# lights.net
KiCad netlist of a schematic drawn in EAGLE
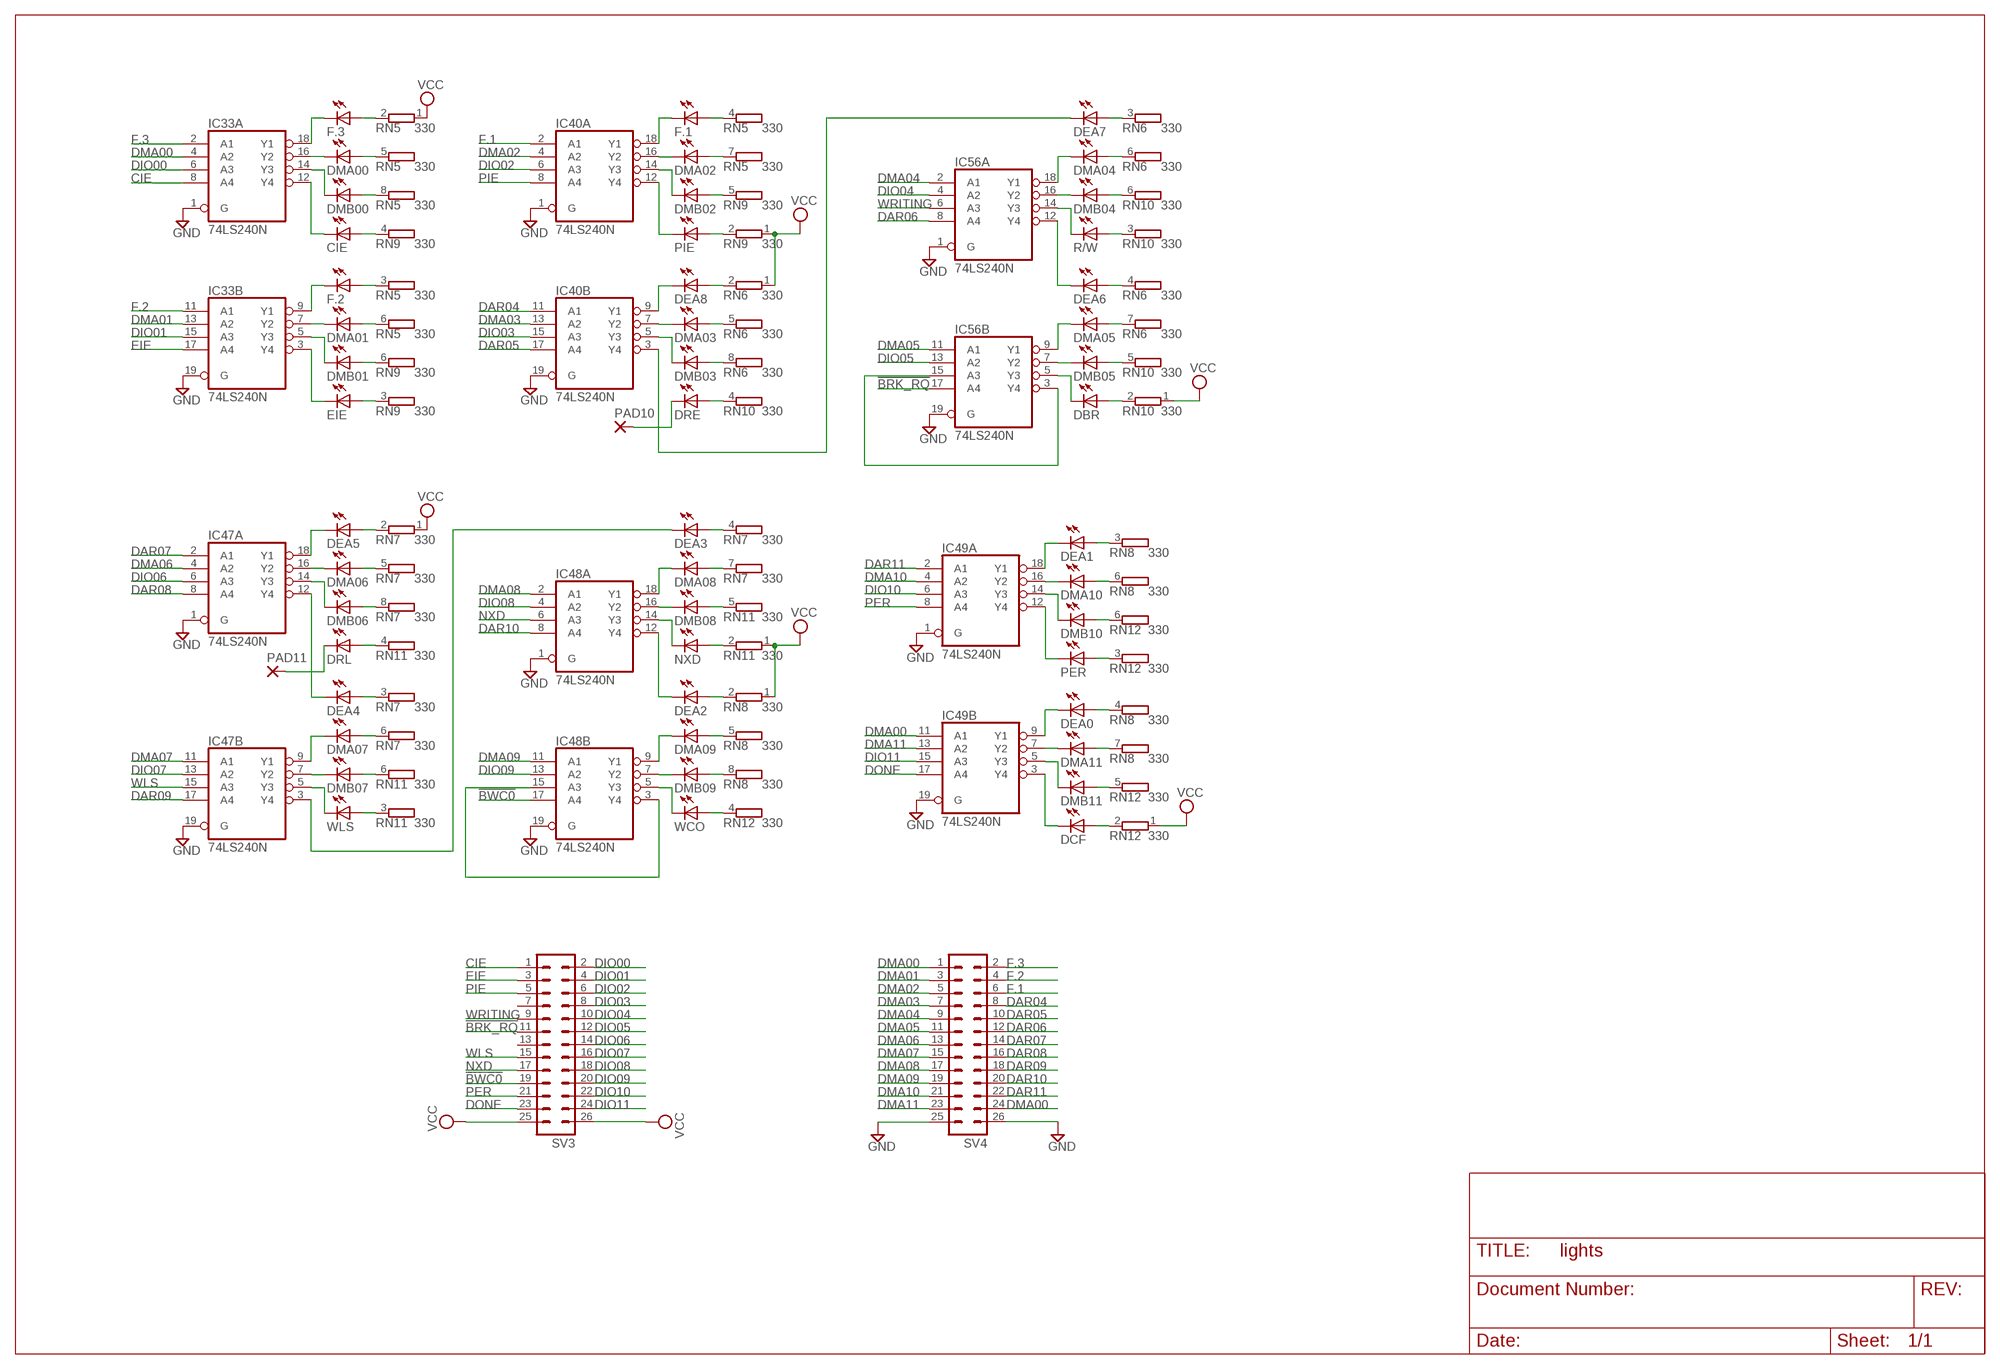
[diagram p0: schematic, sheet 1]

(export (version "E")
  (design (tool "Eeschema 10.0.6"))
  (components
    (comp (ref "CIE")
      (value "LED5MM")
      (footprint "eagle-import:LED5MM")
      (libsource (lib "eagle-import") (part "LED5MM"))
    )
    (comp (ref "DBR")
      (value "LED5MM")
      (footprint "eagle-import:LED5MM")
      (libsource (lib "eagle-import") (part "LED5MM"))
    )
    (comp (ref "DCF")
      (value "LED5MM")
      (footprint "eagle-import:LED5MM")
      (libsource (lib "eagle-import") (part "LED5MM"))
    )
    (comp (ref "DEA0")
      (value "LED5MM")
      (footprint "eagle-import:LED5MM")
      (libsource (lib "eagle-import") (part "LED5MM"))
    )
    (comp (ref "DEA1")
      (value "LED5MM")
      (footprint "eagle-import:LED5MM")
      (libsource (lib "eagle-import") (part "LED5MM"))
    )
    (comp (ref "DEA2")
      (value "LED5MM")
      (footprint "eagle-import:LED5MM")
      (libsource (lib "eagle-import") (part "LED5MM"))
    )
    (comp (ref "DEA3")
      (value "LED5MM")
      (footprint "eagle-import:LED5MM")
      (libsource (lib "eagle-import") (part "LED5MM"))
    )
    (comp (ref "DEA4")
      (value "LED5MM")
      (footprint "eagle-import:LED5MM")
      (libsource (lib "eagle-import") (part "LED5MM"))
    )
    (comp (ref "DEA5")
      (value "LED5MM")
      (footprint "eagle-import:LED5MM")
      (libsource (lib "eagle-import") (part "LED5MM"))
    )
    (comp (ref "DEA6")
      (value "LED5MM")
      (footprint "eagle-import:LED5MM")
      (libsource (lib "eagle-import") (part "LED5MM"))
    )
    (comp (ref "DEA7")
      (value "LED5MM")
      (footprint "eagle-import:LED5MM")
      (libsource (lib "eagle-import") (part "LED5MM"))
    )
    (comp (ref "DEA8")
      (value "LED5MM")
      (footprint "eagle-import:LED5MM")
      (libsource (lib "eagle-import") (part "LED5MM"))
    )
    (comp (ref "DMA00")
      (value "LED5MM")
      (footprint "eagle-import:LED5MM")
      (libsource (lib "eagle-import") (part "LED5MM"))
    )
    (comp (ref "DMA01")
      (value "LED5MM")
      (footprint "eagle-import:LED5MM")
      (libsource (lib "eagle-import") (part "LED5MM"))
    )
    (comp (ref "DMA02")
      (value "LED5MM")
      (footprint "eagle-import:LED5MM")
      (libsource (lib "eagle-import") (part "LED5MM"))
    )
    (comp (ref "DMA03")
      (value "LED5MM")
      (footprint "eagle-import:LED5MM")
      (libsource (lib "eagle-import") (part "LED5MM"))
    )
    (comp (ref "DMA04")
      (value "LED5MM")
      (footprint "eagle-import:LED5MM")
      (libsource (lib "eagle-import") (part "LED5MM"))
    )
    (comp (ref "DMA05")
      (value "LED5MM")
      (footprint "eagle-import:LED5MM")
      (libsource (lib "eagle-import") (part "LED5MM"))
    )
    (comp (ref "DMA06")
      (value "LED5MM")
      (footprint "eagle-import:LED5MM")
      (libsource (lib "eagle-import") (part "LED5MM"))
    )
    (comp (ref "DMA07")
      (value "LED5MM")
      (footprint "eagle-import:LED5MM")
      (libsource (lib "eagle-import") (part "LED5MM"))
    )
    (comp (ref "DMA08")
      (value "LED5MM")
      (footprint "eagle-import:LED5MM")
      (libsource (lib "eagle-import") (part "LED5MM"))
    )
    (comp (ref "DMA09")
      (value "LED5MM")
      (footprint "eagle-import:LED5MM")
      (libsource (lib "eagle-import") (part "LED5MM"))
    )
    (comp (ref "DMA10")
      (value "LED5MM")
      (footprint "eagle-import:LED5MM")
      (libsource (lib "eagle-import") (part "LED5MM"))
    )
    (comp (ref "DMA11")
      (value "LED5MM")
      (footprint "eagle-import:LED5MM")
      (libsource (lib "eagle-import") (part "LED5MM"))
    )
    (comp (ref "DMB00")
      (value "LED5MM")
      (footprint "eagle-import:LED5MM")
      (libsource (lib "eagle-import") (part "LED5MM"))
    )
    (comp (ref "DMB01")
      (value "LED5MM")
      (footprint "eagle-import:LED5MM")
      (libsource (lib "eagle-import") (part "LED5MM"))
    )
    (comp (ref "DMB02")
      (value "LED5MM")
      (footprint "eagle-import:LED5MM")
      (libsource (lib "eagle-import") (part "LED5MM"))
    )
    (comp (ref "DMB03")
      (value "LED5MM")
      (footprint "eagle-import:LED5MM")
      (libsource (lib "eagle-import") (part "LED5MM"))
    )
    (comp (ref "DMB04")
      (value "LED5MM")
      (footprint "eagle-import:LED5MM")
      (libsource (lib "eagle-import") (part "LED5MM"))
    )
    (comp (ref "DMB05")
      (value "LED5MM")
      (footprint "eagle-import:LED5MM")
      (libsource (lib "eagle-import") (part "LED5MM"))
    )
    (comp (ref "DMB06")
      (value "LED5MM")
      (footprint "eagle-import:LED5MM")
      (libsource (lib "eagle-import") (part "LED5MM"))
    )
    (comp (ref "DMB07")
      (value "LED5MM")
      (footprint "eagle-import:LED5MM")
      (libsource (lib "eagle-import") (part "LED5MM"))
    )
    (comp (ref "DMB08")
      (value "LED5MM")
      (footprint "eagle-import:LED5MM")
      (libsource (lib "eagle-import") (part "LED5MM"))
    )
    (comp (ref "DMB09")
      (value "LED5MM")
      (footprint "eagle-import:LED5MM")
      (libsource (lib "eagle-import") (part "LED5MM"))
    )
    (comp (ref "DMB10")
      (value "LED5MM")
      (footprint "eagle-import:LED5MM")
      (libsource (lib "eagle-import") (part "LED5MM"))
    )
    (comp (ref "DMB11")
      (value "LED5MM")
      (footprint "eagle-import:LED5MM")
      (libsource (lib "eagle-import") (part "LED5MM"))
    )
    (comp (ref "DRE")
      (value "LED5MM")
      (footprint "eagle-import:LED5MM")
      (libsource (lib "eagle-import") (part "LED5MM"))
    )
    (comp (ref "DRL")
      (value "LED5MM")
      (footprint "eagle-import:LED5MM")
      (libsource (lib "eagle-import") (part "LED5MM"))
    )
    (comp (ref "EIE")
      (value "LED5MM")
      (footprint "eagle-import:LED5MM")
      (libsource (lib "eagle-import") (part "LED5MM"))
    )
    (comp (ref "F.1")
      (value "LED5MM")
      (footprint "eagle-import:LED5MM")
      (libsource (lib "eagle-import") (part "LED5MM"))
    )
    (comp (ref "F.2")
      (value "LED5MM")
      (footprint "eagle-import:LED5MM")
      (libsource (lib "eagle-import") (part "LED5MM"))
    )
    (comp (ref "F.3")
      (value "LED5MM")
      (footprint "eagle-import:LED5MM")
      (libsource (lib "eagle-import") (part "LED5MM"))
    )
    (comp (ref "IC33")
      (value "74LS240N")
      (footprint "eagle-import:DIL20")
      (libsource (lib "eagle-import") (part "74240NLS"))
    )
    (comp (ref "IC40")
      (value "74LS240N")
      (footprint "eagle-import:DIL20")
      (libsource (lib "eagle-import") (part "74240NLS"))
    )
    (comp (ref "IC47")
      (value "74LS240N")
      (footprint "eagle-import:DIL20")
      (libsource (lib "eagle-import") (part "74240NLS"))
    )
    (comp (ref "IC48")
      (value "74LS240N")
      (footprint "eagle-import:DIL20")
      (libsource (lib "eagle-import") (part "74240NLS"))
    )
    (comp (ref "IC49")
      (value "74LS240N")
      (footprint "eagle-import:DIL20")
      (libsource (lib "eagle-import") (part "74240NLS"))
    )
    (comp (ref "IC56")
      (value "74LS240N")
      (footprint "eagle-import:DIL20")
      (libsource (lib "eagle-import") (part "74240NLS"))
    )
    (comp (ref "NXD")
      (value "LED5MM")
      (footprint "eagle-import:LED5MM")
      (libsource (lib "eagle-import") (part "LED5MM"))
    )
    (comp (ref "PAD10")
      (value "1,6/0,8")
      (footprint "eagle-import:1,6_0,8")
      (libsource (lib "eagle-import") (part "1,6/0,8"))
    )
    (comp (ref "PAD11")
      (value "1,6/0,8")
      (footprint "eagle-import:1,6_0,8")
      (libsource (lib "eagle-import") (part "1,6/0,8"))
    )
    (comp (ref "PER")
      (value "LED5MM")
      (footprint "eagle-import:LED5MM")
      (libsource (lib "eagle-import") (part "LED5MM"))
    )
    (comp (ref "PIE")
      (value "LED5MM")
      (footprint "eagle-import:LED5MM")
      (libsource (lib "eagle-import") (part "LED5MM"))
    )
    (comp (ref "R/W")
      (value "LED5MM")
      (footprint "eagle-import:LED5MM")
      (libsource (lib "eagle-import") (part "LED5MM"))
    )
    (comp (ref "RN5")
      (value "330")
      (footprint "eagle-import:SIL8")
      (libsource (lib "eagle-import") (part "GE07RP"))
    )
    (comp (ref "RN6")
      (value "330")
      (footprint "eagle-import:SIL8")
      (libsource (lib "eagle-import") (part "GE07RP"))
    )
    (comp (ref "RN7")
      (value "330")
      (footprint "eagle-import:SIL8")
      (libsource (lib "eagle-import") (part "GE07RP"))
    )
    (comp (ref "RN8")
      (value "330")
      (footprint "eagle-import:SIL8")
      (libsource (lib "eagle-import") (part "GE07RP"))
    )
    (comp (ref "RN9")
      (value "330")
      (footprint "eagle-import:SIL6")
      (libsource (lib "eagle-import") (part "GE05RP"))
    )
    (comp (ref "RN10")
      (value "330")
      (footprint "eagle-import:SIL6")
      (libsource (lib "eagle-import") (part "GE05RP"))
    )
    (comp (ref "RN11")
      (value "330")
      (footprint "eagle-import:SIL6")
      (libsource (lib "eagle-import") (part "GE05RP"))
    )
    (comp (ref "RN12")
      (value "330")
      (footprint "eagle-import:SIL6")
      (libsource (lib "eagle-import") (part "GE05RP"))
    )
    (comp (ref "SV3")
      (value "MA13-2")
      (footprint "eagle-import:MA13-2")
      (libsource (lib "eagle-import") (part "MA13-2"))
    )
    (comp (ref "SV4")
      (value "MA13-2")
      (footprint "eagle-import:MA13-2")
      (libsource (lib "eagle-import") (part "MA13-2"))
    )
    (comp (ref "WCO")
      (value "LED5MM")
      (footprint "eagle-import:LED5MM")
      (libsource (lib "eagle-import") (part "LED5MM"))
    )
    (comp (ref "WLS")
      (value "LED5MM")
      (footprint "eagle-import:LED5MM")
      (libsource (lib "eagle-import") (part "LED5MM"))
    )
  )
  (nets
    (net (code "1") (name "/CIE") (class "Default")
      (node (ref "IC33") (pin "8") (pinfunction "A4_8") (pintype "input"))
      (node (ref "SV3") (pin "1") (pinfunction "1_1") (pintype "passive"))
    )
    (net (code "2") (name "/DAR04") (class "Default")
      (node (ref "IC40") (pin "11") (pinfunction "A1_11") (pintype "input"))
      (node (ref "SV4") (pin "8") (pinfunction "8_8") (pintype "passive"))
    )
    (net (code "3") (name "/DAR05") (class "Default")
      (node (ref "IC40") (pin "17") (pinfunction "A4_17") (pintype "input"))
      (node (ref "SV4") (pin "10") (pinfunction "10_10") (pintype "passive"))
    )
    (net (code "4") (name "/DAR06") (class "Default")
      (node (ref "IC56") (pin "8") (pinfunction "A4_8") (pintype "input"))
      (node (ref "SV4") (pin "12") (pinfunction "12_12") (pintype "passive"))
    )
    (net (code "5") (name "/DAR07") (class "Default")
      (node (ref "IC47") (pin "2") (pinfunction "A1_2") (pintype "input"))
      (node (ref "SV4") (pin "14") (pinfunction "14_14") (pintype "passive"))
    )
    (net (code "6") (name "/DAR08") (class "Default")
      (node (ref "IC47") (pin "8") (pinfunction "A4_8") (pintype "input"))
      (node (ref "SV4") (pin "16") (pinfunction "16_16") (pintype "passive"))
    )
    (net (code "7") (name "/DAR09") (class "Default")
      (node (ref "IC47") (pin "17") (pinfunction "A4_17") (pintype "input"))
      (node (ref "SV4") (pin "18") (pinfunction "18_18") (pintype "passive"))
    )
    (net (code "8") (name "/DAR10") (class "Default")
      (node (ref "IC48") (pin "8") (pinfunction "A4_8") (pintype "input"))
      (node (ref "SV4") (pin "20") (pinfunction "20_20") (pintype "passive"))
    )
    (net (code "9") (name "/DAR11") (class "Default")
      (node (ref "IC49") (pin "2") (pinfunction "A1_2") (pintype "input"))
      (node (ref "SV4") (pin "22") (pinfunction "22_22") (pintype "passive"))
    )
    (net (code "10") (name "/DIO00") (class "Default")
      (node (ref "IC33") (pin "6") (pinfunction "A3_6") (pintype "input"))
      (node (ref "SV3") (pin "2") (pinfunction "2_2") (pintype "passive"))
    )
    (net (code "11") (name "/DIO01") (class "Default")
      (node (ref "IC33") (pin "15") (pinfunction "A3_15") (pintype "input"))
      (node (ref "SV3") (pin "4") (pinfunction "4_4") (pintype "passive"))
    )
    (net (code "12") (name "/DIO02") (class "Default")
      (node (ref "IC40") (pin "6") (pinfunction "A3_6") (pintype "input"))
      (node (ref "SV3") (pin "6") (pinfunction "6_6") (pintype "passive"))
    )
    (net (code "13") (name "/DIO03") (class "Default")
      (node (ref "IC40") (pin "15") (pinfunction "A3_15") (pintype "input"))
      (node (ref "SV3") (pin "8") (pinfunction "8_8") (pintype "passive"))
    )
    (net (code "14") (name "/DIO04") (class "Default")
      (node (ref "IC56") (pin "4") (pinfunction "A2_4") (pintype "input"))
      (node (ref "SV3") (pin "10") (pinfunction "10_10") (pintype "passive"))
    )
    (net (code "15") (name "/DIO05") (class "Default")
      (node (ref "IC56") (pin "13") (pinfunction "A2_13") (pintype "input"))
      (node (ref "SV3") (pin "12") (pinfunction "12_12") (pintype "passive"))
    )
    (net (code "16") (name "/DIO06") (class "Default")
      (node (ref "IC47") (pin "6") (pinfunction "A3_6") (pintype "input"))
      (node (ref "SV3") (pin "14") (pinfunction "14_14") (pintype "passive"))
    )
    (net (code "17") (name "/DIO07") (class "Default")
      (node (ref "IC47") (pin "13") (pinfunction "A2_13") (pintype "input"))
      (node (ref "SV3") (pin "16") (pinfunction "16_16") (pintype "passive"))
    )
    (net (code "18") (name "/DIO08") (class "Default")
      (node (ref "IC48") (pin "4") (pinfunction "A2_4") (pintype "input"))
      (node (ref "SV3") (pin "18") (pinfunction "18_18") (pintype "passive"))
    )
    (net (code "19") (name "/DIO09") (class "Default")
      (node (ref "IC48") (pin "13") (pinfunction "A2_13") (pintype "input"))
      (node (ref "SV3") (pin "20") (pinfunction "20_20") (pintype "passive"))
    )
    (net (code "20") (name "/DIO10") (class "Default")
      (node (ref "IC49") (pin "6") (pinfunction "A3_6") (pintype "input"))
      (node (ref "SV3") (pin "22") (pinfunction "22_22") (pintype "passive"))
    )
    (net (code "21") (name "/DIO11") (class "Default")
      (node (ref "IC49") (pin "15") (pinfunction "A3_15") (pintype "input"))
      (node (ref "SV3") (pin "24") (pinfunction "24_24") (pintype "passive"))
    )
    (net (code "22") (name "/DMA00") (class "Default")
      (node (ref "IC33") (pin "4") (pinfunction "A2_4") (pintype "input"))
      (node (ref "IC49") (pin "11") (pinfunction "A1_11") (pintype "input"))
      (node (ref "SV4") (pin "1") (pinfunction "1_1") (pintype "passive"))
      (node (ref "SV4") (pin "24") (pinfunction "24_24") (pintype "passive"))
    )
    (net (code "23") (name "/DMA01") (class "Default")
      (node (ref "IC33") (pin "13") (pinfunction "A2_13") (pintype "input"))
      (node (ref "SV4") (pin "3") (pinfunction "3_3") (pintype "passive"))
    )
    (net (code "24") (name "/DMA02") (class "Default")
      (node (ref "IC40") (pin "4") (pinfunction "A2_4") (pintype "input"))
      (node (ref "SV4") (pin "5") (pinfunction "5_5") (pintype "passive"))
    )
    (net (code "25") (name "/DMA03") (class "Default")
      (node (ref "IC40") (pin "13") (pinfunction "A2_13") (pintype "input"))
      (node (ref "SV4") (pin "7") (pinfunction "7_7") (pintype "passive"))
    )
    (net (code "26") (name "/DMA04") (class "Default")
      (node (ref "IC56") (pin "2") (pinfunction "A1_2") (pintype "input"))
      (node (ref "SV4") (pin "9") (pinfunction "9_9") (pintype "passive"))
    )
    (net (code "27") (name "/DMA05") (class "Default")
      (node (ref "IC56") (pin "11") (pinfunction "A1_11") (pintype "input"))
      (node (ref "SV4") (pin "11") (pinfunction "11_11") (pintype "passive"))
    )
    (net (code "28") (name "/DMA06") (class "Default")
      (node (ref "IC47") (pin "4") (pinfunction "A2_4") (pintype "input"))
      (node (ref "SV4") (pin "13") (pinfunction "13_13") (pintype "passive"))
    )
    (net (code "29") (name "/DMA07") (class "Default")
      (node (ref "IC47") (pin "11") (pinfunction "A1_11") (pintype "input"))
      (node (ref "SV4") (pin "15") (pinfunction "15_15") (pintype "passive"))
    )
    (net (code "30") (name "/DMA08") (class "Default")
      (node (ref "IC48") (pin "2") (pinfunction "A1_2") (pintype "input"))
      (node (ref "SV4") (pin "17") (pinfunction "17_17") (pintype "passive"))
    )
    (net (code "31") (name "/DMA09") (class "Default")
      (node (ref "IC48") (pin "11") (pinfunction "A1_11") (pintype "input"))
      (node (ref "SV4") (pin "19") (pinfunction "19_19") (pintype "passive"))
    )
    (net (code "32") (name "/DMA10") (class "Default")
      (node (ref "IC49") (pin "4") (pinfunction "A2_4") (pintype "input"))
      (node (ref "SV4") (pin "21") (pinfunction "21_21") (pintype "passive"))
    )
    (net (code "33") (name "/DMA11") (class "Default")
      (node (ref "IC49") (pin "13") (pinfunction "A2_13") (pintype "input"))
      (node (ref "SV4") (pin "23") (pinfunction "23_23") (pintype "passive"))
    )
    (net (code "34") (name "/DONE") (class "Default")
      (node (ref "IC49") (pin "17") (pinfunction "A4_17") (pintype "input"))
      (node (ref "SV3") (pin "23") (pinfunction "23_23") (pintype "passive"))
    )
    (net (code "35") (name "/EIE") (class "Default")
      (node (ref "IC33") (pin "17") (pinfunction "A4_17") (pintype "input"))
      (node (ref "SV3") (pin "3") (pinfunction "3_3") (pintype "passive"))
    )
    (net (code "36") (name "/F.1") (class "Default")
      (node (ref "IC40") (pin "2") (pinfunction "A1_2") (pintype "input"))
      (node (ref "SV4") (pin "6") (pinfunction "6_6") (pintype "passive"))
    )
    (net (code "37") (name "/F.2") (class "Default")
      (node (ref "IC33") (pin "11") (pinfunction "A1_11") (pintype "input"))
      (node (ref "SV4") (pin "4") (pinfunction "4_4") (pintype "passive"))
    )
    (net (code "38") (name "/F.3") (class "Default")
      (node (ref "IC33") (pin "2") (pinfunction "A1_2") (pintype "input"))
      (node (ref "SV4") (pin "2") (pinfunction "2_2") (pintype "passive"))
    )
    (net (code "39") (name "/NXD") (class "Default")
      (node (ref "IC48") (pin "6") (pinfunction "A3_6") (pintype "input"))
      (node (ref "SV3") (pin "17") (pinfunction "17_17") (pintype "passive"))
    )
    (net (code "40") (name "/PER") (class "Default")
      (node (ref "IC49") (pin "8") (pinfunction "A4_8") (pintype "input"))
      (node (ref "SV3") (pin "21") (pinfunction "21_21") (pintype "passive"))
    )
    (net (code "41") (name "/PIE") (class "Default")
      (node (ref "IC40") (pin "8") (pinfunction "A4_8") (pintype "input"))
      (node (ref "SV3") (pin "5") (pinfunction "5_5") (pintype "passive"))
    )
    (net (code "42") (name "/WLS") (class "Default")
      (node (ref "IC47") (pin "15") (pinfunction "A3_15") (pintype "input"))
      (node (ref "SV3") (pin "15") (pinfunction "15_15") (pintype "passive"))
    )
    (net (code "43") (name "/WRITING") (class "Default")
      (node (ref "IC56") (pin "6") (pinfunction "A3_6") (pintype "input"))
      (node (ref "SV3") (pin "9") (pinfunction "9_9") (pintype "passive"))
    )
    (net (code "44") (name "/~{BRK_RQ}") (class "Default")
      (node (ref "IC56") (pin "17") (pinfunction "A4_17") (pintype "input"))
      (node (ref "SV3") (pin "11") (pinfunction "11_11") (pintype "passive"))
    )
    (net (code "45") (name "/~{BWC0}") (class "Default")
      (node (ref "IC48") (pin "17") (pinfunction "A4_17") (pintype "input"))
      (node (ref "SV3") (pin "19") (pinfunction "19_19") (pintype "passive"))
    )
    (net (code "46") (name "GND") (class "Default")
      (node (ref "IC33") (pin "1") (pinfunction "G_1") (pintype "input"))
      (node (ref "IC33") (pin "19") (pinfunction "G_19") (pintype "input"))
      (node (ref "IC40") (pin "1") (pinfunction "G_1") (pintype "input"))
      (node (ref "IC40") (pin "19") (pinfunction "G_19") (pintype "input"))
      (node (ref "IC47") (pin "1") (pinfunction "G_1") (pintype "input"))
      (node (ref "IC47") (pin "19") (pinfunction "G_19") (pintype "input"))
      (node (ref "IC48") (pin "1") (pinfunction "G_1") (pintype "input"))
      (node (ref "IC48") (pin "19") (pinfunction "G_19") (pintype "input"))
      (node (ref "IC49") (pin "1") (pinfunction "G_1") (pintype "input"))
      (node (ref "IC49") (pin "19") (pinfunction "G_19") (pintype "input"))
      (node (ref "IC56") (pin "1") (pinfunction "G_1") (pintype "input"))
      (node (ref "IC56") (pin "19") (pinfunction "G_19") (pintype "input"))
      (node (ref "SV4") (pin "25") (pinfunction "25_25") (pintype "passive"))
      (node (ref "SV4") (pin "26") (pinfunction "26_26") (pintype "passive"))
    )
    (net (code "47") (name "Net-(CIE-C)") (class "Default")
      (node (ref "CIE") (pin "K") (pinfunction "C_K") (pintype "passive"))
      (node (ref "IC33") (pin "12") (pinfunction "Y4_12") (pintype "tri_state"))
    )
    (net (code "48") (name "Net-(DBR-C)") (class "Default")
      (node (ref "DBR") (pin "K") (pinfunction "C_K") (pintype "passive"))
      (node (ref "IC56") (pin "5") (pinfunction "Y3_5") (pintype "tri_state"))
    )
    (net (code "49") (name "Net-(DBR-PadA)") (class "Default")
      (node (ref "DBR") (pin "A") (pinfunction "A_A") (pintype "passive"))
      (node (ref "RN10") (pin "2") (pinfunction "2_2") (pintype "passive"))
    )
    (net (code "50") (name "Net-(DCF-C)") (class "Default")
      (node (ref "DCF") (pin "K") (pinfunction "C_K") (pintype "passive"))
      (node (ref "IC49") (pin "3") (pinfunction "Y4_3") (pintype "tri_state"))
    )
    (net (code "51") (name "Net-(DCF-PadA)") (class "Default")
      (node (ref "DCF") (pin "A") (pinfunction "A_A") (pintype "passive"))
      (node (ref "RN12") (pin "2") (pinfunction "2_2") (pintype "passive"))
    )
    (net (code "52") (name "Net-(DEA0-C)") (class "Default")
      (node (ref "DEA0") (pin "K") (pinfunction "C_K") (pintype "passive"))
      (node (ref "IC49") (pin "9") (pinfunction "Y1_9") (pintype "tri_state"))
    )
    (net (code "53") (name "Net-(DEA1-C)") (class "Default")
      (node (ref "DEA1") (pin "K") (pinfunction "C_K") (pintype "passive"))
      (node (ref "IC49") (pin "18") (pinfunction "Y1_18") (pintype "tri_state"))
    )
    (net (code "54") (name "Net-(DEA2-C)") (class "Default")
      (node (ref "DEA2") (pin "K") (pinfunction "C_K") (pintype "passive"))
      (node (ref "IC48") (pin "12") (pinfunction "Y4_12") (pintype "tri_state"))
    )
    (net (code "55") (name "Net-(DEA2-PadA)") (class "Default")
      (node (ref "DEA2") (pin "A") (pinfunction "A_A") (pintype "passive"))
      (node (ref "RN8") (pin "2") (pinfunction "2_2") (pintype "passive"))
    )
    (net (code "56") (name "Net-(DEA3-C)") (class "Default")
      (node (ref "DEA3") (pin "K") (pinfunction "C_K") (pintype "passive"))
      (node (ref "IC47") (pin "3") (pinfunction "Y4_3") (pintype "tri_state"))
    )
    (net (code "57") (name "Net-(DEA4-C)") (class "Default")
      (node (ref "DEA4") (pin "K") (pinfunction "C_K") (pintype "passive"))
      (node (ref "IC47") (pin "12") (pinfunction "Y4_12") (pintype "tri_state"))
    )
    (net (code "58") (name "Net-(DEA5-C)") (class "Default")
      (node (ref "DEA5") (pin "K") (pinfunction "C_K") (pintype "passive"))
      (node (ref "IC47") (pin "18") (pinfunction "Y1_18") (pintype "tri_state"))
    )
    (net (code "59") (name "Net-(DEA5-PadA)") (class "Default")
      (node (ref "DEA5") (pin "A") (pinfunction "A_A") (pintype "passive"))
      (node (ref "RN7") (pin "2") (pinfunction "2_2") (pintype "passive"))
    )
    (net (code "60") (name "Net-(DEA6-C)") (class "Default")
      (node (ref "DEA6") (pin "K") (pinfunction "C_K") (pintype "passive"))
      (node (ref "IC56") (pin "12") (pinfunction "Y4_12") (pintype "tri_state"))
    )
    (net (code "61") (name "Net-(DEA7-C)") (class "Default")
      (node (ref "DEA7") (pin "K") (pinfunction "C_K") (pintype "passive"))
      (node (ref "IC40") (pin "3") (pinfunction "Y4_3") (pintype "tri_state"))
    )
    (net (code "62") (name "Net-(DEA8-C)") (class "Default")
      (node (ref "DEA8") (pin "K") (pinfunction "C_K") (pintype "passive"))
      (node (ref "IC40") (pin "9") (pinfunction "Y1_9") (pintype "tri_state"))
    )
    (net (code "63") (name "Net-(DEA8-PadA)") (class "Default")
      (node (ref "DEA8") (pin "A") (pinfunction "A_A") (pintype "passive"))
      (node (ref "RN6") (pin "2") (pinfunction "2_2") (pintype "passive"))
    )
    (net (code "64") (name "Net-(DMA00-C)") (class "Default")
      (node (ref "DMA00") (pin "K") (pinfunction "C_K") (pintype "passive"))
      (node (ref "IC33") (pin "16") (pinfunction "Y2_16") (pintype "tri_state"))
    )
    (net (code "65") (name "Net-(DMA01-C)") (class "Default")
      (node (ref "DMA01") (pin "K") (pinfunction "C_K") (pintype "passive"))
      (node (ref "IC33") (pin "7") (pinfunction "Y2_7") (pintype "tri_state"))
    )
    (net (code "66") (name "Net-(DMA02-C)") (class "Default")
      (node (ref "DMA02") (pin "K") (pinfunction "C_K") (pintype "passive"))
      (node (ref "IC40") (pin "16") (pinfunction "Y2_16") (pintype "tri_state"))
    )
    (net (code "67") (name "Net-(DMA03-C)") (class "Default")
      (node (ref "DMA03") (pin "K") (pinfunction "C_K") (pintype "passive"))
      (node (ref "IC40") (pin "7") (pinfunction "Y2_7") (pintype "tri_state"))
    )
    (net (code "68") (name "Net-(DMA04-C)") (class "Default")
      (node (ref "DMA04") (pin "K") (pinfunction "C_K") (pintype "passive"))
      (node (ref "IC56") (pin "18") (pinfunction "Y1_18") (pintype "tri_state"))
    )
    (net (code "69") (name "Net-(DMA05-C)") (class "Default")
      (node (ref "DMA05") (pin "K") (pinfunction "C_K") (pintype "passive"))
      (node (ref "IC56") (pin "9") (pinfunction "Y1_9") (pintype "tri_state"))
    )
    (net (code "70") (name "Net-(DMA06-C)") (class "Default")
      (node (ref "DMA06") (pin "K") (pinfunction "C_K") (pintype "passive"))
      (node (ref "IC47") (pin "16") (pinfunction "Y2_16") (pintype "tri_state"))
    )
    (net (code "71") (name "Net-(DMA07-C)") (class "Default")
      (node (ref "DMA07") (pin "K") (pinfunction "C_K") (pintype "passive"))
      (node (ref "IC47") (pin "9") (pinfunction "Y1_9") (pintype "tri_state"))
    )
    (net (code "72") (name "Net-(DMA08-C)") (class "Default")
      (node (ref "DMA08") (pin "K") (pinfunction "C_K") (pintype "passive"))
      (node (ref "IC48") (pin "18") (pinfunction "Y1_18") (pintype "tri_state"))
    )
    (net (code "73") (name "Net-(DMA09-C)") (class "Default")
      (node (ref "DMA09") (pin "K") (pinfunction "C_K") (pintype "passive"))
      (node (ref "IC48") (pin "9") (pinfunction "Y1_9") (pintype "tri_state"))
    )
    (net (code "74") (name "Net-(DMA10-C)") (class "Default")
      (node (ref "DMA10") (pin "K") (pinfunction "C_K") (pintype "passive"))
      (node (ref "IC49") (pin "16") (pinfunction "Y2_16") (pintype "tri_state"))
    )
    (net (code "75") (name "Net-(DMA11-C)") (class "Default")
      (node (ref "DMA11") (pin "K") (pinfunction "C_K") (pintype "passive"))
      (node (ref "IC49") (pin "7") (pinfunction "Y2_7") (pintype "tri_state"))
    )
    (net (code "76") (name "Net-(DMB00-C)") (class "Default")
      (node (ref "DMB00") (pin "K") (pinfunction "C_K") (pintype "passive"))
      (node (ref "IC33") (pin "14") (pinfunction "Y3_14") (pintype "tri_state"))
    )
    (net (code "77") (name "Net-(DMB01-C)") (class "Default")
      (node (ref "DMB01") (pin "K") (pinfunction "C_K") (pintype "passive"))
      (node (ref "IC33") (pin "5") (pinfunction "Y3_5") (pintype "tri_state"))
    )
    (net (code "78") (name "Net-(DMB02-C)") (class "Default")
      (node (ref "DMB02") (pin "K") (pinfunction "C_K") (pintype "passive"))
      (node (ref "IC40") (pin "14") (pinfunction "Y3_14") (pintype "tri_state"))
    )
    (net (code "79") (name "Net-(DMB03-C)") (class "Default")
      (node (ref "DMB03") (pin "K") (pinfunction "C_K") (pintype "passive"))
      (node (ref "IC40") (pin "5") (pinfunction "Y3_5") (pintype "tri_state"))
    )
    (net (code "80") (name "Net-(DMB04-C)") (class "Default")
      (node (ref "DMB04") (pin "K") (pinfunction "C_K") (pintype "passive"))
      (node (ref "IC56") (pin "16") (pinfunction "Y2_16") (pintype "tri_state"))
    )
    (net (code "81") (name "Net-(DMB05-C)") (class "Default")
      (node (ref "DMB05") (pin "K") (pinfunction "C_K") (pintype "passive"))
      (node (ref "IC56") (pin "7") (pinfunction "Y2_7") (pintype "tri_state"))
    )
    (net (code "82") (name "Net-(DMB06-C)") (class "Default")
      (node (ref "DMB06") (pin "K") (pinfunction "C_K") (pintype "passive"))
      (node (ref "IC47") (pin "14") (pinfunction "Y3_14") (pintype "tri_state"))
    )
    (net (code "83") (name "Net-(DMB07-C)") (class "Default")
      (node (ref "DMB07") (pin "K") (pinfunction "C_K") (pintype "passive"))
      (node (ref "IC47") (pin "7") (pinfunction "Y2_7") (pintype "tri_state"))
    )
    (net (code "84") (name "Net-(DMB08-C)") (class "Default")
      (node (ref "DMB08") (pin "K") (pinfunction "C_K") (pintype "passive"))
      (node (ref "IC48") (pin "16") (pinfunction "Y2_16") (pintype "tri_state"))
    )
    (net (code "85") (name "Net-(DMB09-C)") (class "Default")
      (node (ref "DMB09") (pin "K") (pinfunction "C_K") (pintype "passive"))
      (node (ref "IC48") (pin "7") (pinfunction "Y2_7") (pintype "tri_state"))
    )
    (net (code "86") (name "Net-(DMB10-C)") (class "Default")
      (node (ref "DMB10") (pin "K") (pinfunction "C_K") (pintype "passive"))
      (node (ref "IC49") (pin "14") (pinfunction "Y3_14") (pintype "tri_state"))
    )
    (net (code "87") (name "Net-(DMB11-C)") (class "Default")
      (node (ref "DMB11") (pin "K") (pinfunction "C_K") (pintype "passive"))
      (node (ref "IC49") (pin "5") (pinfunction "Y3_5") (pintype "tri_state"))
    )
    (net (code "88") (name "Net-(DRE-C)") (class "Default")
      (node (ref "DRE") (pin "K") (pinfunction "C_K") (pintype "passive"))
      (node (ref "PAD10") (pin "1") (pinfunction "P_1") (pintype "passive"))
    )
    (net (code "89") (name "Net-(DRL-C)") (class "Default")
      (node (ref "DRL") (pin "K") (pinfunction "C_K") (pintype "passive"))
      (node (ref "PAD11") (pin "1") (pinfunction "P_1") (pintype "passive"))
    )
    (net (code "90") (name "Net-(EIE-C)") (class "Default")
      (node (ref "EIE") (pin "K") (pinfunction "C_K") (pintype "passive"))
      (node (ref "IC33") (pin "3") (pinfunction "Y4_3") (pintype "tri_state"))
    )
    (net (code "91") (name "Net-(F.1-C)") (class "Default")
      (node (ref "F.1") (pin "K") (pinfunction "C_K") (pintype "passive"))
      (node (ref "IC40") (pin "18") (pinfunction "Y1_18") (pintype "tri_state"))
    )
    (net (code "92") (name "Net-(F.2-C)") (class "Default")
      (node (ref "F.2") (pin "K") (pinfunction "C_K") (pintype "passive"))
      (node (ref "IC33") (pin "9") (pinfunction "Y1_9") (pintype "tri_state"))
    )
    (net (code "93") (name "Net-(F.3-C)") (class "Default")
      (node (ref "F.3") (pin "K") (pinfunction "C_K") (pintype "passive"))
      (node (ref "IC33") (pin "18") (pinfunction "Y1_18") (pintype "tri_state"))
    )
    (net (code "94") (name "Net-(F.3-PadA)") (class "Default")
      (node (ref "F.3") (pin "A") (pinfunction "A_A") (pintype "passive"))
      (node (ref "RN5") (pin "2") (pinfunction "2_2") (pintype "passive"))
    )
    (net (code "95") (name "Net-(IC40A-Y4)") (class "Default")
      (node (ref "IC40") (pin "12") (pinfunction "Y4_12") (pintype "tri_state"))
      (node (ref "PIE") (pin "K") (pinfunction "C_K") (pintype "passive"))
    )
    (net (code "96") (name "Net-(IC47B-Y3)") (class "Default")
      (node (ref "IC47") (pin "5") (pinfunction "Y3_5") (pintype "tri_state"))
      (node (ref "WLS") (pin "K") (pinfunction "C_K") (pintype "passive"))
    )
    (net (code "97") (name "Net-(IC48A-Y3)") (class "Default")
      (node (ref "IC48") (pin "14") (pinfunction "Y3_14") (pintype "tri_state"))
      (node (ref "NXD") (pin "K") (pinfunction "C_K") (pintype "passive"))
    )
    (net (code "98") (name "Net-(IC48B-A3)") (class "Default")
      (node (ref "IC48") (pin "15") (pinfunction "A3_15") (pintype "input"))
      (node (ref "IC48") (pin "3") (pinfunction "Y4_3") (pintype "tri_state"))
    )
    (net (code "99") (name "Net-(IC48B-Y3)") (class "Default")
      (node (ref "IC48") (pin "5") (pinfunction "Y3_5") (pintype "tri_state"))
      (node (ref "WCO") (pin "K") (pinfunction "C_K") (pintype "passive"))
    )
    (net (code "100") (name "Net-(IC49A-Y4)") (class "Default")
      (node (ref "IC49") (pin "12") (pinfunction "Y4_12") (pintype "tri_state"))
      (node (ref "PER") (pin "K") (pinfunction "C_K") (pintype "passive"))
    )
    (net (code "101") (name "Net-(IC56A-Y3)") (class "Default")
      (node (ref "IC56") (pin "14") (pinfunction "Y3_14") (pintype "tri_state"))
      (node (ref "R/W") (pin "K") (pinfunction "C_K") (pintype "passive"))
    )
    (net (code "102") (name "Net-(IC56B-A3)") (class "Default")
      (node (ref "IC56") (pin "15") (pinfunction "A3_15") (pintype "input"))
      (node (ref "IC56") (pin "3") (pinfunction "Y4_3") (pintype "tri_state"))
    )
    (net (code "103") (name "Net-(NXD-PadA)") (class "Default")
      (node (ref "NXD") (pin "A") (pinfunction "A_A") (pintype "passive"))
      (node (ref "RN11") (pin "2") (pinfunction "2_2") (pintype "passive"))
    )
    (net (code "104") (name "Net-(PIE-PadA)") (class "Default")
      (node (ref "PIE") (pin "A") (pinfunction "A_A") (pintype "passive"))
      (node (ref "RN9") (pin "2") (pinfunction "2_2") (pintype "passive"))
    )
    (net (code "105") (name "Net-(RN5B-2)") (class "Default")
      (node (ref "F.2") (pin "A") (pinfunction "A_A") (pintype "passive"))
      (node (ref "RN5") (pin "3") (pinfunction "2_3") (pintype "passive"))
    )
    (net (code "106") (name "Net-(RN5C-2)") (class "Default")
      (node (ref "F.1") (pin "A") (pinfunction "A_A") (pintype "passive"))
      (node (ref "RN5") (pin "4") (pinfunction "2_4") (pintype "passive"))
    )
    (net (code "107") (name "Net-(RN5D-2)") (class "Default")
      (node (ref "DMA00") (pin "A") (pinfunction "A_A") (pintype "passive"))
      (node (ref "RN5") (pin "5") (pinfunction "2_5") (pintype "passive"))
    )
    (net (code "108") (name "Net-(RN5E-2)") (class "Default")
      (node (ref "DMA01") (pin "A") (pinfunction "A_A") (pintype "passive"))
      (node (ref "RN5") (pin "6") (pinfunction "2_6") (pintype "passive"))
    )
    (net (code "109") (name "Net-(RN5F-2)") (class "Default")
      (node (ref "DMA02") (pin "A") (pinfunction "A_A") (pintype "passive"))
      (node (ref "RN5") (pin "7") (pinfunction "2_7") (pintype "passive"))
    )
    (net (code "110") (name "Net-(RN5G-2)") (class "Default")
      (node (ref "DMB00") (pin "A") (pinfunction "A_A") (pintype "passive"))
      (node (ref "RN5") (pin "8") (pinfunction "2_8") (pintype "passive"))
    )
    (net (code "111") (name "Net-(RN6B-2)") (class "Default")
      (node (ref "DEA7") (pin "A") (pinfunction "A_A") (pintype "passive"))
      (node (ref "RN6") (pin "3") (pinfunction "2_3") (pintype "passive"))
    )
    (net (code "112") (name "Net-(RN6C-2)") (class "Default")
      (node (ref "DEA6") (pin "A") (pinfunction "A_A") (pintype "passive"))
      (node (ref "RN6") (pin "4") (pinfunction "2_4") (pintype "passive"))
    )
    (net (code "113") (name "Net-(RN6D-2)") (class "Default")
      (node (ref "DMA03") (pin "A") (pinfunction "A_A") (pintype "passive"))
      (node (ref "RN6") (pin "5") (pinfunction "2_5") (pintype "passive"))
    )
    (net (code "114") (name "Net-(RN6E-2)") (class "Default")
      (node (ref "DMA04") (pin "A") (pinfunction "A_A") (pintype "passive"))
      (node (ref "RN6") (pin "6") (pinfunction "2_6") (pintype "passive"))
    )
    (net (code "115") (name "Net-(RN6F-2)") (class "Default")
      (node (ref "DMA05") (pin "A") (pinfunction "A_A") (pintype "passive"))
      (node (ref "RN6") (pin "7") (pinfunction "2_7") (pintype "passive"))
    )
    (net (code "116") (name "Net-(RN6G-2)") (class "Default")
      (node (ref "DMB03") (pin "A") (pinfunction "A_A") (pintype "passive"))
      (node (ref "RN6") (pin "8") (pinfunction "2_8") (pintype "passive"))
    )
    (net (code "117") (name "Net-(RN7B-2)") (class "Default")
      (node (ref "DEA4") (pin "A") (pinfunction "A_A") (pintype "passive"))
      (node (ref "RN7") (pin "3") (pinfunction "2_3") (pintype "passive"))
    )
    (net (code "118") (name "Net-(RN7C-2)") (class "Default")
      (node (ref "DEA3") (pin "A") (pinfunction "A_A") (pintype "passive"))
      (node (ref "RN7") (pin "4") (pinfunction "2_4") (pintype "passive"))
    )
    (net (code "119") (name "Net-(RN7D-2)") (class "Default")
      (node (ref "DMA06") (pin "A") (pinfunction "A_A") (pintype "passive"))
      (node (ref "RN7") (pin "5") (pinfunction "2_5") (pintype "passive"))
    )
    (net (code "120") (name "Net-(RN7E-2)") (class "Default")
      (node (ref "DMA07") (pin "A") (pinfunction "A_A") (pintype "passive"))
      (node (ref "RN7") (pin "6") (pinfunction "2_6") (pintype "passive"))
    )
    (net (code "121") (name "Net-(RN7F-2)") (class "Default")
      (node (ref "DMA08") (pin "A") (pinfunction "A_A") (pintype "passive"))
      (node (ref "RN7") (pin "7") (pinfunction "2_7") (pintype "passive"))
    )
    (net (code "122") (name "Net-(RN7G-2)") (class "Default")
      (node (ref "DMB06") (pin "A") (pinfunction "A_A") (pintype "passive"))
      (node (ref "RN7") (pin "8") (pinfunction "2_8") (pintype "passive"))
    )
    (net (code "123") (name "Net-(RN8B-2)") (class "Default")
      (node (ref "DEA1") (pin "A") (pinfunction "A_A") (pintype "passive"))
      (node (ref "RN8") (pin "3") (pinfunction "2_3") (pintype "passive"))
    )
    (net (code "124") (name "Net-(RN8C-2)") (class "Default")
      (node (ref "DEA0") (pin "A") (pinfunction "A_A") (pintype "passive"))
      (node (ref "RN8") (pin "4") (pinfunction "2_4") (pintype "passive"))
    )
    (net (code "125") (name "Net-(RN8D-2)") (class "Default")
      (node (ref "DMA09") (pin "A") (pinfunction "A_A") (pintype "passive"))
      (node (ref "RN8") (pin "5") (pinfunction "2_5") (pintype "passive"))
    )
    (net (code "126") (name "Net-(RN8E-2)") (class "Default")
      (node (ref "DMA10") (pin "A") (pinfunction "A_A") (pintype "passive"))
      (node (ref "RN8") (pin "6") (pinfunction "2_6") (pintype "passive"))
    )
    (net (code "127") (name "Net-(RN8F-2)") (class "Default")
      (node (ref "DMA11") (pin "A") (pinfunction "A_A") (pintype "passive"))
      (node (ref "RN8") (pin "7") (pinfunction "2_7") (pintype "passive"))
    )
    (net (code "128") (name "Net-(RN8G-2)") (class "Default")
      (node (ref "DMB09") (pin "A") (pinfunction "A_A") (pintype "passive"))
      (node (ref "RN8") (pin "8") (pinfunction "2_8") (pintype "passive"))
    )
    (net (code "129") (name "Net-(RN9B-2)") (class "Default")
      (node (ref "EIE") (pin "A") (pinfunction "A_A") (pintype "passive"))
      (node (ref "RN9") (pin "3") (pinfunction "2_3") (pintype "passive"))
    )
    (net (code "130") (name "Net-(RN9C-2)") (class "Default")
      (node (ref "CIE") (pin "A") (pinfunction "A_A") (pintype "passive"))
      (node (ref "RN9") (pin "4") (pinfunction "2_4") (pintype "passive"))
    )
    (net (code "131") (name "Net-(RN9D-2)") (class "Default")
      (node (ref "DMB02") (pin "A") (pinfunction "A_A") (pintype "passive"))
      (node (ref "RN9") (pin "5") (pinfunction "2_5") (pintype "passive"))
    )
    (net (code "132") (name "Net-(RN9E-2)") (class "Default")
      (node (ref "DMB01") (pin "A") (pinfunction "A_A") (pintype "passive"))
      (node (ref "RN9") (pin "6") (pinfunction "2_6") (pintype "passive"))
    )
    (net (code "133") (name "Net-(RN10B-2)") (class "Default")
      (node (ref "R/W") (pin "A") (pinfunction "A_A") (pintype "passive"))
      (node (ref "RN10") (pin "3") (pinfunction "2_3") (pintype "passive"))
    )
    (net (code "134") (name "Net-(RN10C-2)") (class "Default")
      (node (ref "DRE") (pin "A") (pinfunction "A_A") (pintype "passive"))
      (node (ref "RN10") (pin "4") (pinfunction "2_4") (pintype "passive"))
    )
    (net (code "135") (name "Net-(RN10D-2)") (class "Default")
      (node (ref "DMB05") (pin "A") (pinfunction "A_A") (pintype "passive"))
      (node (ref "RN10") (pin "5") (pinfunction "2_5") (pintype "passive"))
    )
    (net (code "136") (name "Net-(RN10E-2)") (class "Default")
      (node (ref "DMB04") (pin "A") (pinfunction "A_A") (pintype "passive"))
      (node (ref "RN10") (pin "6") (pinfunction "2_6") (pintype "passive"))
    )
    (net (code "137") (name "Net-(RN11B-2)") (class "Default")
      (node (ref "RN11") (pin "3") (pinfunction "2_3") (pintype "passive"))
      (node (ref "WLS") (pin "A") (pinfunction "A_A") (pintype "passive"))
    )
    (net (code "138") (name "Net-(RN11C-2)") (class "Default")
      (node (ref "DRL") (pin "A") (pinfunction "A_A") (pintype "passive"))
      (node (ref "RN11") (pin "4") (pinfunction "2_4") (pintype "passive"))
    )
    (net (code "139") (name "Net-(RN11D-2)") (class "Default")
      (node (ref "DMB08") (pin "A") (pinfunction "A_A") (pintype "passive"))
      (node (ref "RN11") (pin "5") (pinfunction "2_5") (pintype "passive"))
    )
    (net (code "140") (name "Net-(RN11E-2)") (class "Default")
      (node (ref "DMB07") (pin "A") (pinfunction "A_A") (pintype "passive"))
      (node (ref "RN11") (pin "6") (pinfunction "2_6") (pintype "passive"))
    )
    (net (code "141") (name "Net-(RN12B-2)") (class "Default")
      (node (ref "PER") (pin "A") (pinfunction "A_A") (pintype "passive"))
      (node (ref "RN12") (pin "3") (pinfunction "2_3") (pintype "passive"))
    )
    (net (code "142") (name "Net-(RN12C-2)") (class "Default")
      (node (ref "RN12") (pin "4") (pinfunction "2_4") (pintype "passive"))
      (node (ref "WCO") (pin "A") (pinfunction "A_A") (pintype "passive"))
    )
    (net (code "143") (name "Net-(RN12D-2)") (class "Default")
      (node (ref "DMB11") (pin "A") (pinfunction "A_A") (pintype "passive"))
      (node (ref "RN12") (pin "5") (pinfunction "2_5") (pintype "passive"))
    )
    (net (code "144") (name "Net-(RN12E-2)") (class "Default")
      (node (ref "DMB10") (pin "A") (pinfunction "A_A") (pintype "passive"))
      (node (ref "RN12") (pin "6") (pinfunction "2_6") (pintype "passive"))
    )
    (net (code "145") (name "VCC") (class "Default")
      (node (ref "RN10") (pin "1") (pinfunction "1_1") (pintype "passive"))
      (node (ref "RN11") (pin "1") (pinfunction "1_1") (pintype "passive"))
      (node (ref "RN12") (pin "1") (pinfunction "1_1") (pintype "passive"))
      (node (ref "RN5") (pin "1") (pinfunction "1_1") (pintype "passive"))
      (node (ref "RN6") (pin "1") (pinfunction "1_1") (pintype "passive"))
      (node (ref "RN7") (pin "1") (pinfunction "1_1") (pintype "passive"))
      (node (ref "RN8") (pin "1") (pinfunction "1_1") (pintype "passive"))
      (node (ref "RN9") (pin "1") (pinfunction "1_1") (pintype "passive"))
      (node (ref "SV3") (pin "25") (pinfunction "25_25") (pintype "passive"))
      (node (ref "SV3") (pin "26") (pinfunction "26_26") (pintype "passive"))
    )
    (net (code "146") (name "unconnected-(SV3-Pad7)") (class "Default")
      (node (ref "SV3") (pin "7") (pinfunction "7_7") (pintype "passive"))
    )
    (net (code "147") (name "unconnected-(SV3-Pad13)") (class "Default")
      (node (ref "SV3") (pin "13") (pinfunction "13_13") (pintype "passive"))
    )
  )
)
